# IOT_NodeMCU8266-1_v3.net
KiCad netlist of a schematic drawn in EAGLE
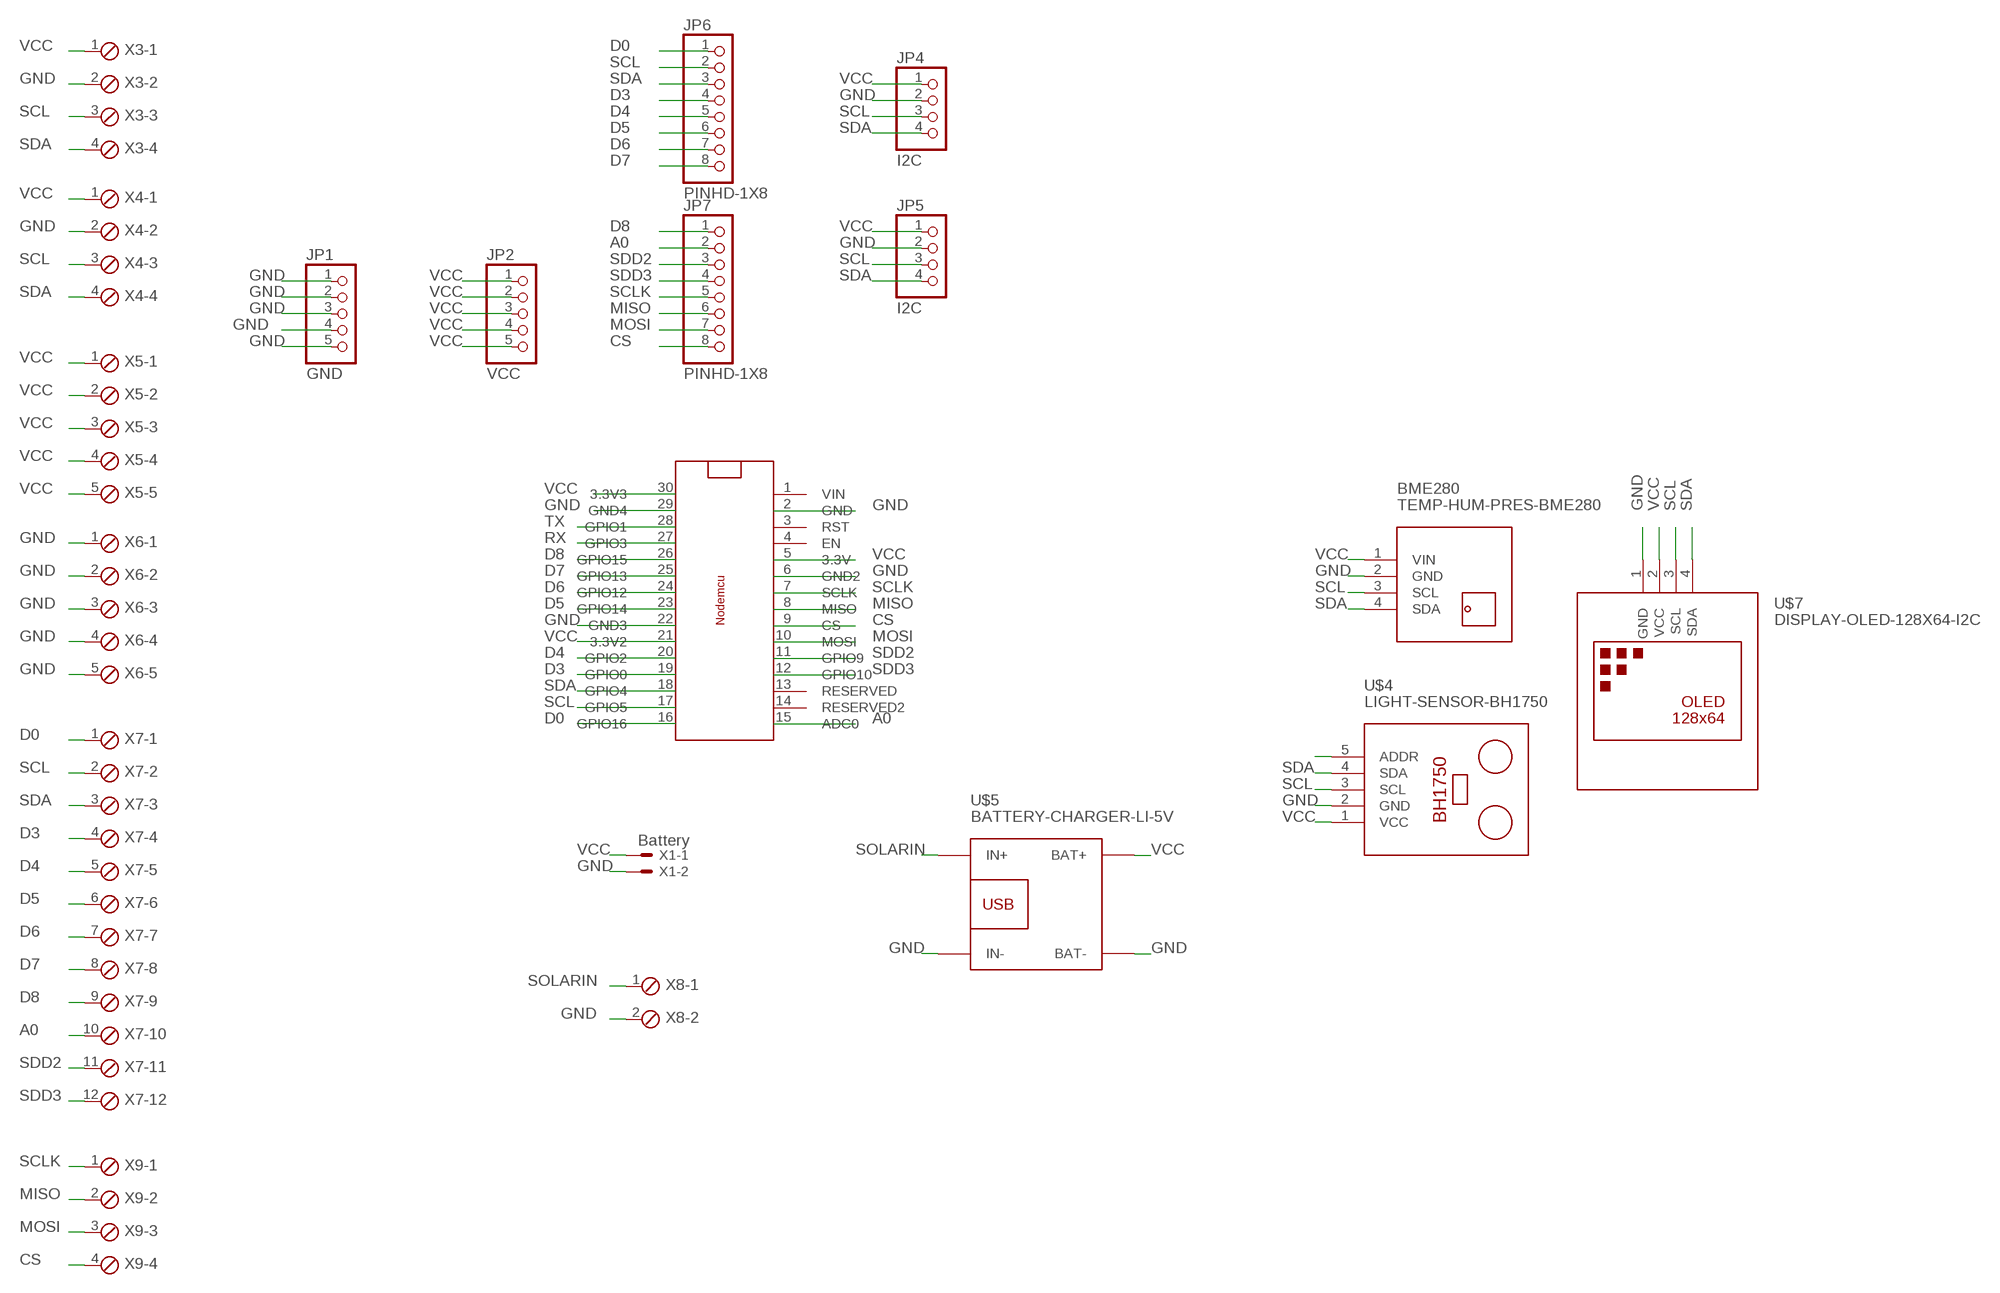
[diagram p0: schematic, sheet 1]

(export (version "E")
  (design (tool "Eeschema 10.0.6"))
  (components
    (comp (ref "BME280")
      (value "TEMP-HUM-PRES-BME280")
      (footprint "eagle-import:TEMP-HUM-PRES-BME280")
      (libsource (lib "eagle-import") (part "TEMP-HUM-PRES-BME280"))
    )
    (comp (ref "JP1")
      (value "GND")
      (footprint "eagle-import:1X05")
      (libsource (lib "eagle-import") (part "PINHD-1X5"))
    )
    (comp (ref "JP2")
      (value "VCC")
      (footprint "eagle-import:1X05")
      (libsource (lib "eagle-import") (part "PINHD-1X5"))
    )
    (comp (ref "JP4")
      (value "I2C")
      (footprint "eagle-import:1X04")
      (libsource (lib "eagle-import") (part "PINHD-1X4"))
    )
    (comp (ref "JP5")
      (value "I2C")
      (footprint "eagle-import:1X04")
      (libsource (lib "eagle-import") (part "PINHD-1X4"))
    )
    (comp (ref "JP6")
      (value "PINHD-1X8")
      (footprint "eagle-import:1X08")
      (libsource (lib "eagle-import") (part "PINHD-1X8"))
    )
    (comp (ref "JP7")
      (value "PINHD-1X8")
      (footprint "eagle-import:1X08")
      (libsource (lib "eagle-import") (part "PINHD-1X8"))
    )
    (comp (ref "U$1")
      (value "NODEMCUESP8266")
      (footprint "eagle-import:NODEMCUESP8266")
      (libsource (lib "eagle-import") (part "NODEMCUESP8266"))
    )
    (comp (ref "U$4")
      (value "LIGHT-SENSOR-BH1750")
      (footprint "eagle-import:LIGHT-SENSOR-BH1750")
      (libsource (lib "eagle-import") (part "LIGHT-SENSOR-BH1750"))
    )
    (comp (ref "U$5")
      (value "BATTERY-CHARGER-LI-5V")
      (footprint "eagle-import:BATTERY-CHARGER-LI-5V")
      (libsource (lib "eagle-import") (part "BATTERY-CHARGER-LI-5V"))
    )
    (comp (ref "U$7")
      (value "DISPLAY-OLED-128X64-I2C")
      (footprint "eagle-import:DISPLAY-OLED-128X64-I2C")
      (libsource (lib "eagle-import") (part "DISPLAY-OLED-128X64-I2C"))
    )
    (comp (ref "X1")
      (value "Battery")
      (footprint "eagle-import:53047-02")
      (fields (field (name "MF") "MOLEX") (field (name "MPN") "53047-0210"))
      (libsource (lib "eagle-import") (part "53?-02047"))
    )
    (comp (ref "X3")
      (value "MPT4")
      (footprint "eagle-import:4POL254")
      (libsource (lib "eagle-import") (part "MPT4"))
    )
    (comp (ref "X4")
      (value "MPT4")
      (footprint "eagle-import:4POL254")
      (libsource (lib "eagle-import") (part "MPT4"))
    )
    (comp (ref "X5")
      (value "MPT5")
      (footprint "eagle-import:5POL254")
      (libsource (lib "eagle-import") (part "MPT5"))
    )
    (comp (ref "X6")
      (value "MPT5")
      (footprint "eagle-import:5POL254")
      (libsource (lib "eagle-import") (part "MPT5"))
    )
    (comp (ref "X7")
      (value "MPT12")
      (footprint "eagle-import:12POL254")
      (libsource (lib "eagle-import") (part "MPT12"))
    )
    (comp (ref "X8")
      (value "MPT2")
      (footprint "eagle-import:2POL254")
      (libsource (lib "eagle-import") (part "MPT2"))
    )
    (comp (ref "X9")
      (value "MPT4")
      (footprint "eagle-import:4POL254")
      (libsource (lib "eagle-import") (part "MPT4"))
    )
  )
  (nets
    (net (code "1") (name "/A0") (class "Default")
      (node (ref "JP7") (pin "2") (pinfunction "2_2") (pintype "passive"))
      (node (ref "U$1") (pin "15") (pinfunction "ADC0_15") (pintype "bidirectional"))
      (node (ref "X7") (pin "10") (pinfunction "1_10") (pintype "passive"))
    )
    (net (code "2") (name "/CS") (class "Default")
      (node (ref "JP7") (pin "8") (pinfunction "8_8") (pintype "passive"))
      (node (ref "U$1") (pin "9") (pinfunction "CS_9") (pintype "bidirectional"))
      (node (ref "X9") (pin "4") (pinfunction "1_4") (pintype "passive"))
    )
    (net (code "3") (name "/D0") (class "Default")
      (node (ref "JP6") (pin "1") (pinfunction "1_1") (pintype "passive"))
      (node (ref "U$1") (pin "16") (pinfunction "GPIO16_16") (pintype "bidirectional"))
      (node (ref "X7") (pin "1") (pinfunction "1_1") (pintype "passive"))
    )
    (net (code "4") (name "/D3") (class "Default")
      (node (ref "JP6") (pin "4") (pinfunction "4_4") (pintype "passive"))
      (node (ref "U$1") (pin "19") (pinfunction "GPIO0_19") (pintype "bidirectional"))
      (node (ref "X7") (pin "4") (pinfunction "1_4") (pintype "passive"))
    )
    (net (code "5") (name "/D4") (class "Default")
      (node (ref "JP6") (pin "5") (pinfunction "5_5") (pintype "passive"))
      (node (ref "U$1") (pin "20") (pinfunction "GPIO2_20") (pintype "bidirectional"))
      (node (ref "X7") (pin "5") (pinfunction "1_5") (pintype "passive"))
    )
    (net (code "6") (name "/D5") (class "Default")
      (node (ref "JP6") (pin "6") (pinfunction "6_6") (pintype "passive"))
      (node (ref "U$1") (pin "23") (pinfunction "GPIO14_23") (pintype "bidirectional"))
      (node (ref "X7") (pin "6") (pinfunction "1_6") (pintype "passive"))
    )
    (net (code "7") (name "/D6") (class "Default")
      (node (ref "JP6") (pin "7") (pinfunction "7_7") (pintype "passive"))
      (node (ref "U$1") (pin "24") (pinfunction "GPIO12_24") (pintype "bidirectional"))
      (node (ref "X7") (pin "7") (pinfunction "1_7") (pintype "passive"))
    )
    (net (code "8") (name "/D7") (class "Default")
      (node (ref "JP6") (pin "8") (pinfunction "8_8") (pintype "passive"))
      (node (ref "U$1") (pin "25") (pinfunction "GPIO13_25") (pintype "bidirectional"))
      (node (ref "X7") (pin "8") (pinfunction "1_8") (pintype "passive"))
    )
    (net (code "9") (name "/D8") (class "Default")
      (node (ref "JP7") (pin "1") (pinfunction "1_1") (pintype "passive"))
      (node (ref "U$1") (pin "26") (pinfunction "GPIO15_26") (pintype "bidirectional"))
      (node (ref "X7") (pin "9") (pinfunction "1_9") (pintype "passive"))
    )
    (net (code "10") (name "/GND") (class "Default")
      (node (ref "BME280") (pin "2") (pinfunction "GND_2") (pintype "power_in"))
      (node (ref "JP1") (pin "1") (pinfunction "1_1") (pintype "passive"))
      (node (ref "JP1") (pin "2") (pinfunction "2_2") (pintype "passive"))
      (node (ref "JP1") (pin "3") (pinfunction "3_3") (pintype "passive"))
      (node (ref "JP1") (pin "4") (pinfunction "4_4") (pintype "passive"))
      (node (ref "JP1") (pin "5") (pinfunction "5_5") (pintype "passive"))
      (node (ref "JP4") (pin "2") (pinfunction "2_2") (pintype "passive"))
      (node (ref "JP5") (pin "2") (pinfunction "2_2") (pintype "passive"))
      (node (ref "U$1") (pin "2") (pinfunction "GND_2") (pintype "bidirectional"))
      (node (ref "U$1") (pin "22") (pinfunction "GND3_22") (pintype "bidirectional"))
      (node (ref "U$1") (pin "29") (pinfunction "GND4_29") (pintype "bidirectional"))
      (node (ref "U$1") (pin "6") (pinfunction "GND2_6") (pintype "bidirectional"))
      (node (ref "U$4") (pin "2") (pinfunction "GND_2") (pintype "power_in"))
      (node (ref "U$5") (pin "BAT-") (pinfunction "BAT-_BAT-") (pintype "bidirectional"))
      (node (ref "U$5") (pin "IN-") (pinfunction "IN-_IN-") (pintype "bidirectional"))
      (node (ref "U$7") (pin "1") (pinfunction "GND_1") (pintype "power_in"))
      (node (ref "X1") (pin "2") (pinfunction "S_2") (pintype "passive"))
      (node (ref "X3") (pin "2") (pinfunction "1_2") (pintype "passive"))
      (node (ref "X4") (pin "2") (pinfunction "1_2") (pintype "passive"))
      (node (ref "X6") (pin "1") (pinfunction "1_1") (pintype "passive"))
      (node (ref "X6") (pin "2") (pinfunction "1_2") (pintype "passive"))
      (node (ref "X6") (pin "3") (pinfunction "1_3") (pintype "passive"))
      (node (ref "X6") (pin "4") (pinfunction "1_4") (pintype "passive"))
      (node (ref "X6") (pin "5") (pinfunction "1_5") (pintype "passive"))
      (node (ref "X8") (pin "2") (pinfunction "1_2") (pintype "passive"))
    )
    (net (code "11") (name "/MISO") (class "Default")
      (node (ref "JP7") (pin "6") (pinfunction "6_6") (pintype "passive"))
      (node (ref "U$1") (pin "8") (pinfunction "MISO_8") (pintype "bidirectional"))
      (node (ref "X9") (pin "2") (pinfunction "1_2") (pintype "passive"))
    )
    (net (code "12") (name "/MOSI") (class "Default")
      (node (ref "JP7") (pin "7") (pinfunction "7_7") (pintype "passive"))
      (node (ref "U$1") (pin "10") (pinfunction "MOSI_10") (pintype "bidirectional"))
      (node (ref "X9") (pin "3") (pinfunction "1_3") (pintype "passive"))
    )
    (net (code "13") (name "/RX") (class "Default")
      (node (ref "U$1") (pin "27") (pinfunction "GPIO3_27") (pintype "bidirectional"))
    )
    (net (code "14") (name "/SCL") (class "Default")
      (node (ref "BME280") (pin "3") (pinfunction "SCL_3") (pintype "bidirectional"))
      (node (ref "JP4") (pin "3") (pinfunction "3_3") (pintype "passive"))
      (node (ref "JP5") (pin "3") (pinfunction "3_3") (pintype "passive"))
      (node (ref "JP6") (pin "2") (pinfunction "2_2") (pintype "passive"))
      (node (ref "U$1") (pin "17") (pinfunction "GPIO5_17") (pintype "bidirectional"))
      (node (ref "U$4") (pin "3") (pinfunction "SCL_3") (pintype "bidirectional"))
      (node (ref "U$7") (pin "3") (pinfunction "SCL_3") (pintype "bidirectional"))
      (node (ref "X3") (pin "3") (pinfunction "1_3") (pintype "passive"))
      (node (ref "X4") (pin "3") (pinfunction "1_3") (pintype "passive"))
      (node (ref "X7") (pin "2") (pinfunction "1_2") (pintype "passive"))
    )
    (net (code "15") (name "/SCLK") (class "Default")
      (node (ref "JP7") (pin "5") (pinfunction "5_5") (pintype "passive"))
      (node (ref "U$1") (pin "7") (pinfunction "SCLK_7") (pintype "bidirectional"))
      (node (ref "X9") (pin "1") (pinfunction "1_1") (pintype "passive"))
    )
    (net (code "16") (name "/SDA") (class "Default")
      (node (ref "BME280") (pin "4") (pinfunction "SDA_4") (pintype "bidirectional"))
      (node (ref "JP4") (pin "4") (pinfunction "4_4") (pintype "passive"))
      (node (ref "JP5") (pin "4") (pinfunction "4_4") (pintype "passive"))
      (node (ref "JP6") (pin "3") (pinfunction "3_3") (pintype "passive"))
      (node (ref "U$1") (pin "18") (pinfunction "GPIO4_18") (pintype "bidirectional"))
      (node (ref "U$4") (pin "4") (pinfunction "SDA_4") (pintype "bidirectional"))
      (node (ref "U$7") (pin "4") (pinfunction "SDA_4") (pintype "bidirectional"))
      (node (ref "X3") (pin "4") (pinfunction "1_4") (pintype "passive"))
      (node (ref "X4") (pin "4") (pinfunction "1_4") (pintype "passive"))
      (node (ref "X7") (pin "3") (pinfunction "1_3") (pintype "passive"))
    )
    (net (code "17") (name "/SDD2") (class "Default")
      (node (ref "JP7") (pin "3") (pinfunction "3_3") (pintype "passive"))
      (node (ref "U$1") (pin "11") (pinfunction "GPIO9_11") (pintype "bidirectional"))
      (node (ref "X7") (pin "11") (pinfunction "1_11") (pintype "passive"))
    )
    (net (code "18") (name "/SDD3") (class "Default")
      (node (ref "JP7") (pin "4") (pinfunction "4_4") (pintype "passive"))
      (node (ref "U$1") (pin "12") (pinfunction "GPIO10_12") (pintype "bidirectional"))
      (node (ref "X7") (pin "12") (pinfunction "1_12") (pintype "passive"))
    )
    (net (code "19") (name "/SOLARIN") (class "Default")
      (node (ref "U$5") (pin "IN+") (pinfunction "IN+_IN+") (pintype "bidirectional"))
      (node (ref "X8") (pin "1") (pinfunction "1_1") (pintype "passive"))
    )
    (net (code "20") (name "/TX") (class "Default")
      (node (ref "U$1") (pin "28") (pinfunction "GPIO1_28") (pintype "bidirectional"))
    )
    (net (code "21") (name "/VCC") (class "Default")
      (node (ref "BME280") (pin "1") (pinfunction "VIN_1") (pintype "power_in"))
      (node (ref "JP2") (pin "1") (pinfunction "1_1") (pintype "passive"))
      (node (ref "JP2") (pin "2") (pinfunction "2_2") (pintype "passive"))
      (node (ref "JP2") (pin "3") (pinfunction "3_3") (pintype "passive"))
      (node (ref "JP2") (pin "4") (pinfunction "4_4") (pintype "passive"))
      (node (ref "JP2") (pin "5") (pinfunction "5_5") (pintype "passive"))
      (node (ref "JP4") (pin "1") (pinfunction "1_1") (pintype "passive"))
      (node (ref "JP5") (pin "1") (pinfunction "1_1") (pintype "passive"))
      (node (ref "U$1") (pin "21") (pinfunction "3.3V2_21") (pintype "bidirectional"))
      (node (ref "U$1") (pin "30") (pinfunction "3.3V3_30") (pintype "bidirectional"))
      (node (ref "U$1") (pin "5") (pinfunction "3.3V_5") (pintype "bidirectional"))
      (node (ref "U$4") (pin "1") (pinfunction "VCC_1") (pintype "power_in"))
      (node (ref "U$5") (pin "BAT+") (pinfunction "BAT+_BAT+") (pintype "bidirectional"))
      (node (ref "U$7") (pin "2") (pinfunction "VCC_2") (pintype "power_in"))
      (node (ref "X1") (pin "1") (pinfunction "S_1") (pintype "passive"))
      (node (ref "X3") (pin "1") (pinfunction "1_1") (pintype "passive"))
      (node (ref "X4") (pin "1") (pinfunction "1_1") (pintype "passive"))
      (node (ref "X5") (pin "1") (pinfunction "1_1") (pintype "passive"))
      (node (ref "X5") (pin "2") (pinfunction "1_2") (pintype "passive"))
      (node (ref "X5") (pin "3") (pinfunction "1_3") (pintype "passive"))
      (node (ref "X5") (pin "4") (pinfunction "1_4") (pintype "passive"))
      (node (ref "X5") (pin "5") (pinfunction "1_5") (pintype "passive"))
    )
    (net (code "22") (name "unconnected-(U$1-EN-Pad4)") (class "Default")
      (node (ref "U$1") (pin "4") (pinfunction "EN_4") (pintype "bidirectional"))
    )
    (net (code "23") (name "unconnected-(U$1-RESERVED-Pad13)") (class "Default")
      (node (ref "U$1") (pin "13") (pinfunction "RESERVED_13") (pintype "bidirectional"))
    )
    (net (code "24") (name "unconnected-(U$1-RESERVED2-Pad14)") (class "Default")
      (node (ref "U$1") (pin "14") (pinfunction "RESERVED2_14") (pintype "bidirectional"))
    )
    (net (code "25") (name "unconnected-(U$1-RST-Pad3)") (class "Default")
      (node (ref "U$1") (pin "3") (pinfunction "RST_3") (pintype "bidirectional"))
    )
    (net (code "26") (name "unconnected-(U$1-VIN-Pad1)") (class "Default")
      (node (ref "U$1") (pin "1") (pinfunction "VIN_1") (pintype "bidirectional"))
    )
    (net (code "27") (name "unconnected-(U$4-ADDR-Pad5)") (class "Default")
      (node (ref "U$4") (pin "5") (pinfunction "ADDR_5") (pintype "bidirectional"))
    )
  )
)
